# EXPANDER_I2C.net
KiCad netlist of a schematic drawn in Altium Designer
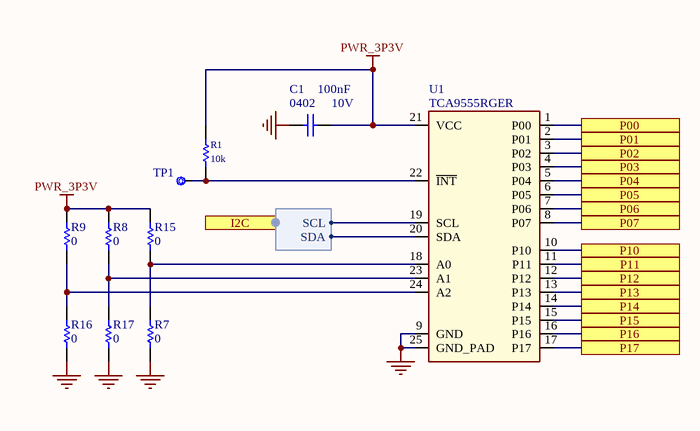
[diagram p0: EXPANDER_I2C.SchDoc]

(export (version "E")
  (design (tool "Eeschema 10.0.6"))
  (components
    (comp (ref "C1")
      (value "100nF")
      (footprint "CAP-0402")
      (description "CAP CHIP 0402 100nF 10% 10V X5R")
      (fields
        (field (name "PART NUMBER") "GRM155R61A104KA01J")
        (field (name "CASE CODE (IMPERIAL)") "0402")
        (field (name "VOLTAGE") "10V")
        (field (name "TOLERANCE") "10%")
      )
      (libsource (lib "Clean") (part "CAP"))
    )
    (comp (ref "R1")
      (value "10k")
      (footprint "RES-0402")
      (description "RES CHIP 0402 10k 1% 1/16W")
      (fields (field (name "PART NUMBER") "CRCW040210K0FKED") (field (name "MANUFACTURER") "Vishay"))
      (libsource (lib "Clean") (part "RES"))
    )
    (comp (ref "R7")
      (value "0")
      (footprint "RES-0402")
      (description "RES CHIP 0402 0R 1/16W")
      (fields (field (name "POWER") "62.5mW") (field (name "MANUFACTURER") "Vishay"))
      (libsource (lib "Clean") (part "RES"))
    )
    (comp (ref "R8")
      (value "0")
      (footprint "RES-0402")
      (description "RES CHIP 0402 0R 1/16W")
      (fields (field (name "POWER") "62.5mW") (field (name "MANUFACTURER") "Vishay"))
      (libsource (lib "Clean") (part "RES"))
    )
    (comp (ref "R9")
      (value "0")
      (footprint "RES-0402")
      (description "RES CHIP 0402 0R 1/16W")
      (fields (field (name "POWER") "62.5mW") (field (name "MANUFACTURER") "Vishay"))
      (libsource (lib "Clean") (part "RES"))
    )
    (comp (ref "R15")
      (value "0")
      (footprint "RES-0402")
      (description "RES CHIP 0402 0R 1/16W")
      (fields (field (name "POWER") "62.5mW") (field (name "MANUFACTURER") "Vishay"))
      (libsource (lib "Clean") (part "RES"))
    )
    (comp (ref "R16")
      (value "0")
      (footprint "RES-0402")
      (description "RES CHIP 0402 0R 1/16W")
      (fields (field (name "POWER") "62.5mW") (field (name "MANUFACTURER") "Vishay"))
      (libsource (lib "Clean") (part "RES"))
    )
    (comp (ref "R17")
      (value "0")
      (footprint "RES-0402")
      (description "RES CHIP 0402 0R 1/16W")
      (fields (field (name "POWER") "62.5mW") (field (name "MANUFACTURER") "Vishay"))
      (libsource (lib "Clean") (part "RES"))
    )
    (comp (ref "TP1")
      (value "Test point 1.00mm")
      (footprint "TP-1.00MM")
      (fields (field (name "MANUFACTURER") "This is not a component"))
      (libsource (lib "Clean") (part "TESTPOINT"))
    )
    (comp (ref "U1")
      (value "TCA9555RGER")
      (footprint "PQFN50P400X400X100_HS-25N")
      (description "IC 16b I2C EXPANDER with INTERRUPT")
      (fields (field (name "MANUFACTURER") "Texas Instruments") (field (name "LCSC PART #") "C2869248"))
      (libsource (lib "Clean") (part "TCA9555RGER"))
    )
  )
  (nets
    (net (code "2") (name "/P00") (class "Default")
      (node (ref "U1") (pin "1") (pinfunction "P00_1") (pintype "passive"))
    )
    (net (code "3") (name "/P01") (class "Default")
      (node (ref "U1") (pin "2") (pinfunction "P01_2") (pintype "passive"))
    )
    (net (code "4") (name "/P02") (class "Default")
      (node (ref "U1") (pin "3") (pinfunction "P02_3") (pintype "passive"))
    )
    (net (code "5") (name "/P03") (class "Default")
      (node (ref "U1") (pin "4") (pinfunction "P03_4") (pintype "passive"))
    )
    (net (code "6") (name "/P04") (class "Default")
      (node (ref "U1") (pin "5") (pinfunction "P04_5") (pintype "passive"))
    )
    (net (code "7") (name "/P05") (class "Default")
      (node (ref "U1") (pin "6") (pinfunction "P05_6") (pintype "passive"))
    )
    (net (code "8") (name "/P06") (class "Default")
      (node (ref "U1") (pin "7") (pinfunction "P06_7") (pintype "passive"))
    )
    (net (code "9") (name "/P07") (class "Default")
      (node (ref "U1") (pin "8") (pinfunction "P07_8") (pintype "passive"))
    )
    (net (code "10") (name "/P10") (class "Default")
      (node (ref "U1") (pin "10") (pinfunction "P10_10") (pintype "passive"))
    )
    (net (code "11") (name "/P11") (class "Default")
      (node (ref "U1") (pin "11") (pinfunction "P11_11") (pintype "passive"))
    )
    (net (code "12") (name "/P12") (class "Default")
      (node (ref "U1") (pin "12") (pinfunction "P12_12") (pintype "passive"))
    )
    (net (code "13") (name "/P13") (class "Default")
      (node (ref "U1") (pin "13") (pinfunction "P13_13") (pintype "passive"))
    )
    (net (code "14") (name "/P14") (class "Default")
      (node (ref "U1") (pin "14") (pinfunction "P14_14") (pintype "passive"))
    )
    (net (code "15") (name "/P15") (class "Default")
      (node (ref "U1") (pin "15") (pinfunction "P15_15") (pintype "passive"))
    )
    (net (code "16") (name "/P16") (class "Default")
      (node (ref "U1") (pin "16") (pinfunction "P16_16") (pintype "passive"))
    )
    (net (code "17") (name "/P17") (class "Default")
      (node (ref "U1") (pin "17") (pinfunction "P17_17") (pintype "passive"))
    )
    (net (code "18") (name "/SCL") (class "Default")
      (node (ref "U1") (pin "19") (pinfunction "SCL_19") (pintype "passive"))
    )
    (net (code "19") (name "/SDA") (class "Default")
      (node (ref "U1") (pin "20") (pinfunction "SDA_20") (pintype "passive"))
    )
    (net (code "21") (name "GND") (class "Default")
      (node (ref "C1") (pin "1") (pinfunction "1_1") (pintype "passive"))
      (node (ref "R16") (pin "2") (pinfunction "2_2") (pintype "passive"))
      (node (ref "R17") (pin "2") (pinfunction "2_2") (pintype "passive"))
      (node (ref "R7") (pin "2") (pinfunction "2_2") (pintype "passive"))
      (node (ref "U1") (pin "25") (pinfunction "GND_PAD_25") (pintype "passive"))
      (node (ref "U1") (pin "9") (pinfunction "GND_9") (pintype "passive"))
    )
    (net (code "22") (name "Net-(U1-A0)") (class "Default")
      (node (ref "R15") (pin "2") (pinfunction "2_2") (pintype "passive"))
      (node (ref "R7") (pin "1") (pinfunction "1_1") (pintype "passive"))
      (node (ref "U1") (pin "18") (pinfunction "A0_18") (pintype "passive"))
    )
    (net (code "23") (name "Net-(U1-A1)") (class "Default")
      (node (ref "R17") (pin "1") (pinfunction "1_1") (pintype "passive"))
      (node (ref "R8") (pin "2") (pinfunction "2_2") (pintype "passive"))
      (node (ref "U1") (pin "23") (pinfunction "A1_23") (pintype "passive"))
    )
    (net (code "24") (name "Net-(U1-A2)") (class "Default")
      (node (ref "R16") (pin "1") (pinfunction "1_1") (pintype "passive"))
      (node (ref "R9") (pin "2") (pinfunction "2_2") (pintype "passive"))
      (node (ref "U1") (pin "24") (pinfunction "A2_24") (pintype "passive"))
    )
    (net (code "25") (name "Net-(U1-~{INT})") (class "Default")
      (node (ref "R1") (pin "1") (pinfunction "1_1") (pintype "passive"))
      (node (ref "TP1") (pin "X") (pinfunction "X_X") (pintype "passive"))
      (node (ref "U1") (pin "22") (pinfunction "~{INT}_22") (pintype "passive"))
    )
    (net (code "26") (name "PWR_3P3V") (class "Default")
      (node (ref "C1") (pin "2") (pinfunction "2_2") (pintype "passive"))
      (node (ref "R1") (pin "2") (pinfunction "2_2") (pintype "passive"))
      (node (ref "R15") (pin "1") (pinfunction "1_1") (pintype "passive"))
      (node (ref "R8") (pin "1") (pinfunction "1_1") (pintype "passive"))
      (node (ref "R9") (pin "1") (pinfunction "1_1") (pintype "passive"))
      (node (ref "U1") (pin "21") (pinfunction "VCC_21") (pintype "passive"))
    )
  )
)
